# NANO103.net
KiCad netlist of a schematic drawn in Altium Designer
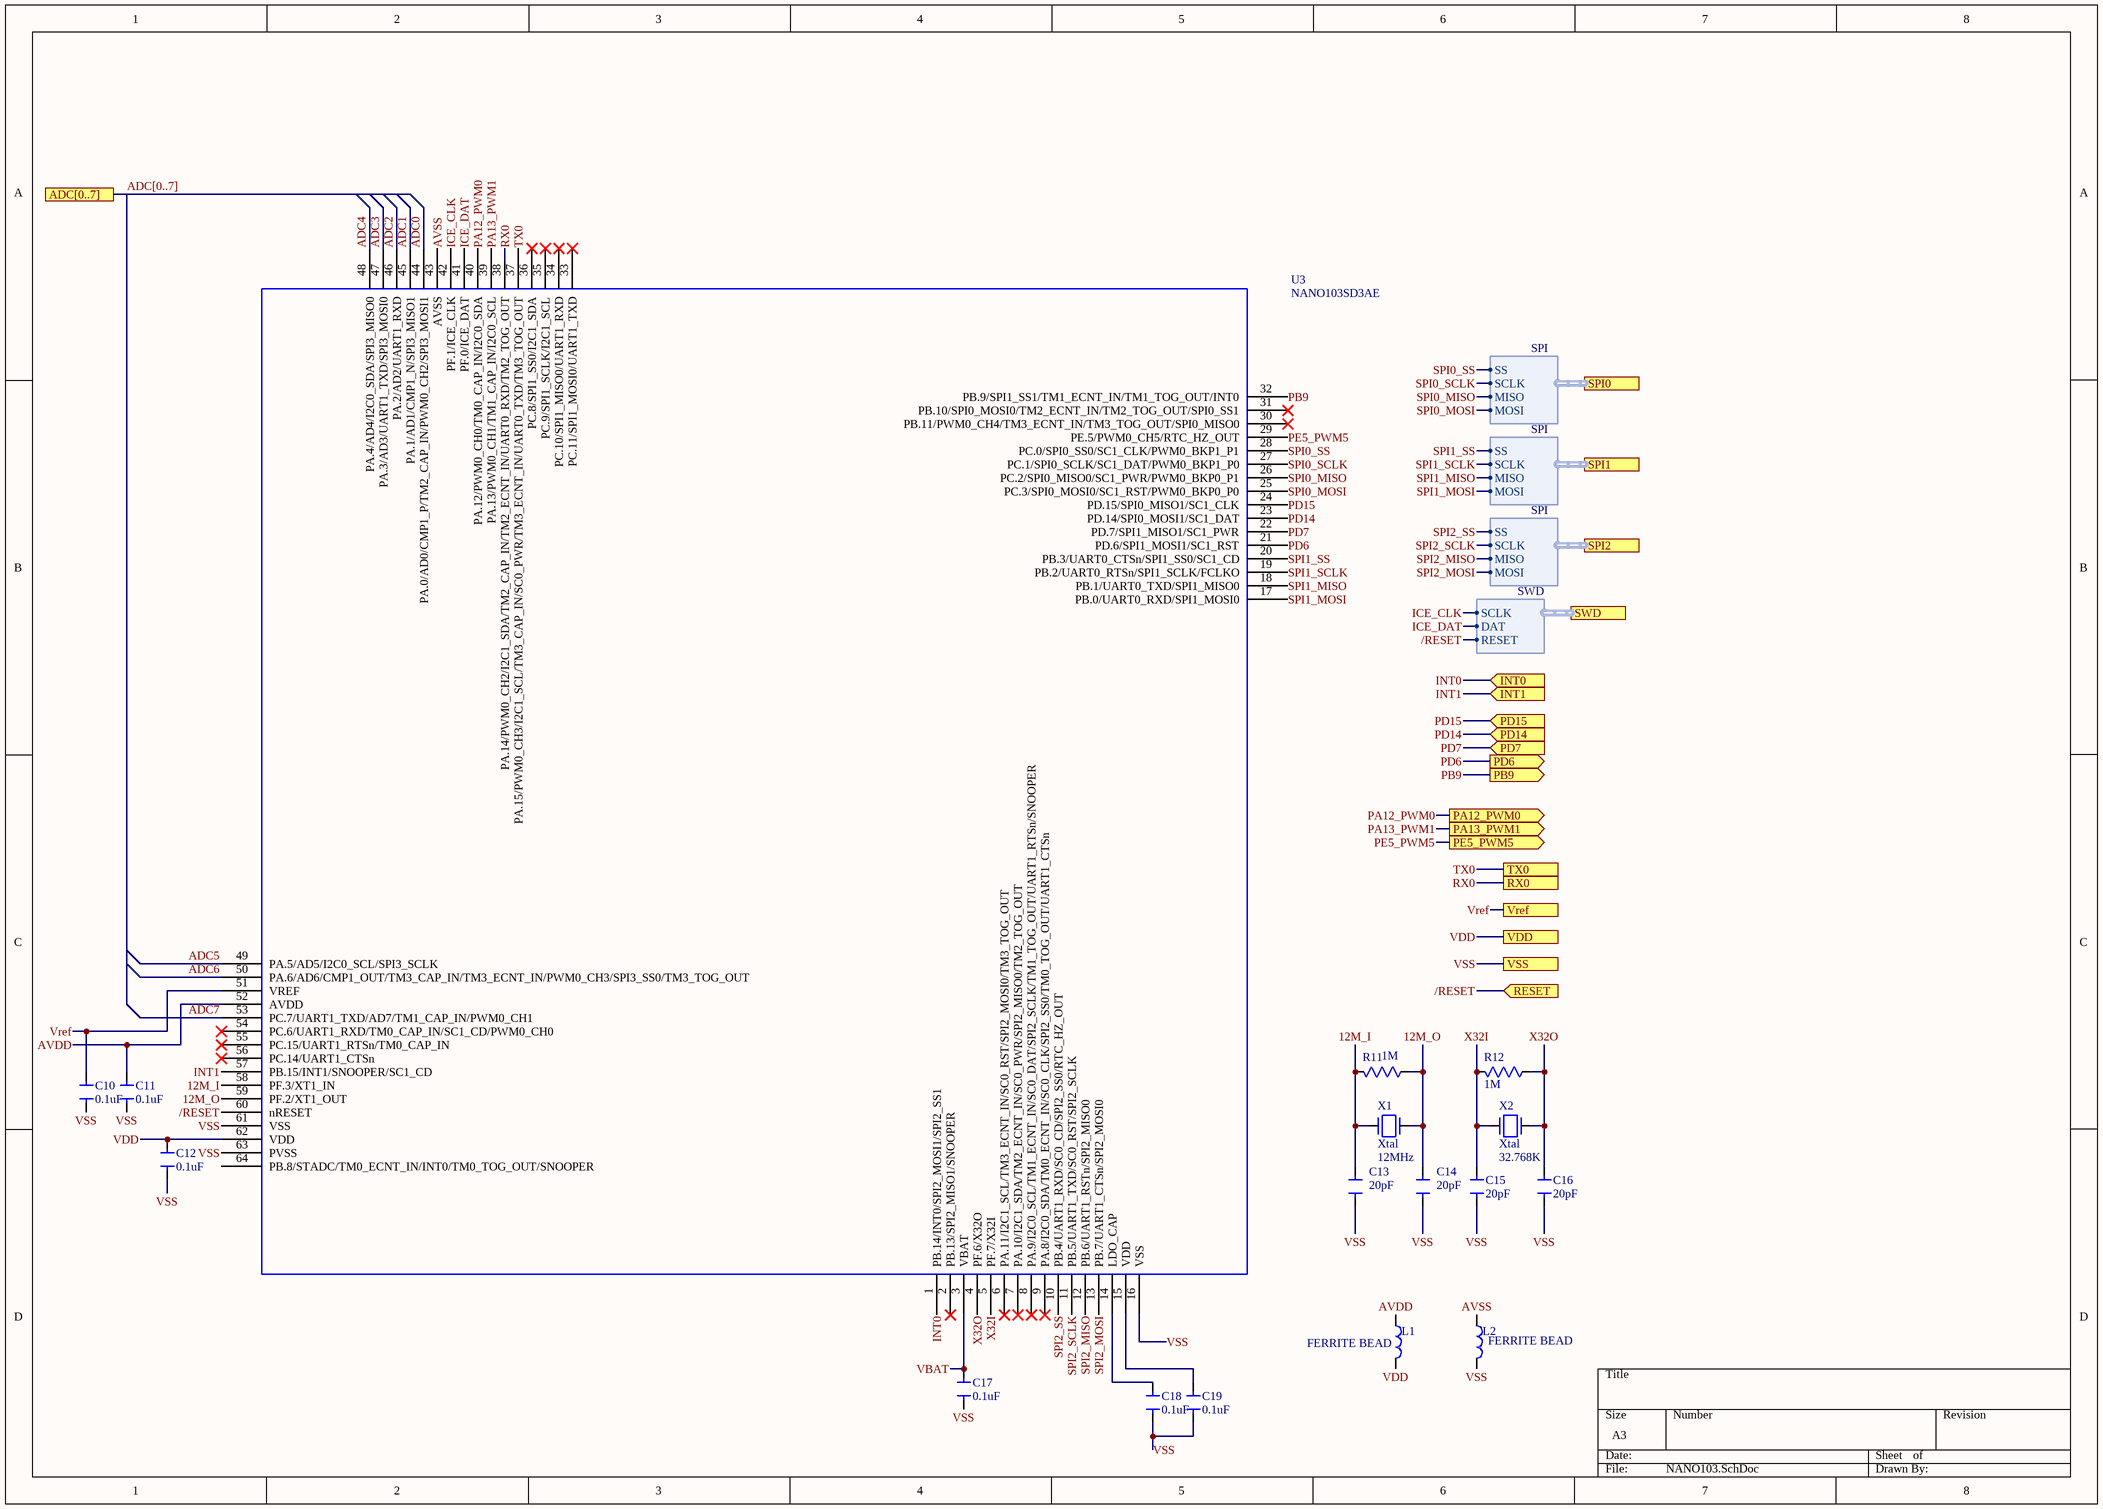
[diagram p0: NANO103.SchDoc]

(export (version "E")
  (design (tool "Eeschema 10.0.6"))
  (components
    (comp (ref "C10")
      (value "0.1uF")
      (footprint "CAP_0402")
      (fields (field (name "Comment") "Cap"))
      (libsource (lib "ZGR") (part "Cap"))
    )
    (comp (ref "C11")
      (value "0.1uF")
      (footprint "CAP_0402")
      (fields (field (name "Comment") "Cap"))
      (libsource (lib "ZGR") (part "Cap"))
    )
    (comp (ref "C12")
      (value "0.1uF")
      (footprint "CAP_0402")
      (fields (field (name "Comment") "Cap"))
      (libsource (lib "ZGR") (part "Cap"))
    )
    (comp (ref "C13")
      (value "20pF")
      (footprint "CAP_0402")
      (fields (field (name "Comment") "Cap"))
      (libsource (lib "ZGR") (part "Cap"))
    )
    (comp (ref "C14")
      (value "20pF")
      (footprint "CAP_0402")
      (fields (field (name "Comment") "Cap"))
      (libsource (lib "ZGR") (part "Cap"))
    )
    (comp (ref "C15")
      (value "20pF")
      (footprint "CAP_0402")
      (fields (field (name "Comment") "Cap"))
      (libsource (lib "ZGR") (part "Cap"))
    )
    (comp (ref "C16")
      (value "20pF")
      (footprint "CAP_0402")
      (fields (field (name "Comment") "Cap"))
      (libsource (lib "ZGR") (part "Cap"))
    )
    (comp (ref "C17")
      (value "0.1uF")
      (footprint "CAP_0402")
      (fields (field (name "Comment") "Cap"))
      (libsource (lib "ZGR") (part "Cap"))
    )
    (comp (ref "C18")
      (value "0.1uF")
      (footprint "CAP_0402")
      (fields (field (name "Comment") "Cap"))
      (libsource (lib "ZGR") (part "Cap"))
    )
    (comp (ref "C19")
      (value "0.1uF")
      (footprint "CAP_0402")
      (fields (field (name "Comment") "Cap"))
      (libsource (lib "ZGR") (part "Cap"))
    )
    (comp (ref "L1")
      (value "FERRITE BEAD")
      (footprint "Inductor_0603")
      (libsource (lib "ZGR") (part "Inductor"))
    )
    (comp (ref "L2")
      (value "FERRITE BEAD")
      (footprint "Inductor_0603")
      (libsource (lib "ZGR") (part "Inductor"))
    )
    (comp (ref "R11")
      (value "1M")
      (footprint "RES_0402")
      (fields (field (name "Comment") "Res"))
      (libsource (lib "ZGR") (part "Res"))
    )
    (comp (ref "R12")
      (value "1M")
      (footprint "RES_0402")
      (fields (field (name "Comment") "Res"))
      (libsource (lib "ZGR") (part "Res"))
    )
    (comp (ref "U3")
      (value "NANO103SD3AE")
      (footprint "MCU_LQFP_64_7x7")
      (libsource (lib "NUVOTON") (part "NANO103SD3AE"))
    )
    (comp (ref "X1")
      (value "Xtal")
      (footprint "2520S")
      (fields (field (name "ALTIUM_VALUE") "12MHz"))
      (libsource (lib "ZGR") (part "Xtal"))
    )
    (comp (ref "X2")
      (value "Xtal")
      (footprint "FC-135")
      (fields (field (name "ALTIUM_VALUE") "32.768K"))
      (libsource (lib "ZGR") (part "Xtal"))
    )
  )
  (nets
    (net (code "3") (name "/12M_I") (class "Default")
      (node (ref "C13") (pin "1") (pinfunction "1_1") (pintype "passive"))
      (node (ref "R11") (pin "1") (pinfunction "1_1") (pintype "passive"))
      (node (ref "U3") (pin "58") (pinfunction "PF.3/XT1_IN_58") (pintype "passive"))
      (node (ref "X1") (pin "2") (pintype "passive"))
    )
    (net (code "4") (name "/12M_O") (class "Default")
      (node (ref "C14") (pin "1") (pinfunction "1_1") (pintype "passive"))
      (node (ref "R11") (pin "2") (pinfunction "2_2") (pintype "passive"))
      (node (ref "U3") (pin "59") (pinfunction "PF.2/XT1_OUT_59") (pintype "passive"))
      (node (ref "X1") (pin "1") (pintype "passive"))
    )
    (net (code "5") (name "/ADC0") (class "Default")
      (node (ref "U3") (pin "44") (pinfunction "PA.0/AD0/CMP1_P/TM2_CAP_IN/PWM0_CH2/SPI3_MOSI1_44") (pintype "passive"))
    )
    (net (code "6") (name "/ADC1") (class "Default")
      (node (ref "U3") (pin "45") (pinfunction "PA.1/AD1/CMP1_N/SPI3_MISO1_45") (pintype "passive"))
    )
    (net (code "7") (name "/ADC2") (class "Default")
      (node (ref "U3") (pin "46") (pinfunction "PA.2/AD2/UART1_RXD_46") (pintype "passive"))
    )
    (net (code "8") (name "/ADC3") (class "Default")
      (node (ref "U3") (pin "47") (pinfunction "PA.3/AD3/UART1_TXD/SPI3_MOSI0_47") (pintype "passive"))
    )
    (net (code "9") (name "/ADC4") (class "Default")
      (node (ref "U3") (pin "48") (pinfunction "PA.4/AD4/I2C0_SDA/SPI3_MISO0_48") (pintype "passive"))
    )
    (net (code "10") (name "/ADC5") (class "Default")
      (node (ref "U3") (pin "49") (pinfunction "PA.5/AD5/I2C0_SCL/SPI3_SCLK_49") (pintype "passive"))
    )
    (net (code "11") (name "/ADC6") (class "Default")
      (node (ref "U3") (pin "50") (pinfunction "PA.6/AD6/CMP1_OUT/TM3_CAP_IN/TM3_ECNT_IN/PWM0_CH3/SPI3_SS0/TM3_TOG_OUT_50") (pintype "passive"))
    )
    (net (code "12") (name "/ADC7") (class "Default")
      (node (ref "U3") (pin "53") (pinfunction "PC.7/UART1_TXD/AD7/TM1_CAP_IN/PWM0_CH1_53") (pintype "passive"))
    )
    (net (code "14") (name "/AVDD") (class "Default")
      (node (ref "C11") (pin "2") (pinfunction "2_2") (pintype "passive"))
      (node (ref "L1") (pin "1") (pinfunction "1_1") (pintype "passive"))
      (node (ref "U3") (pin "52") (pinfunction "AVDD_52") (pintype "passive"))
    )
    (net (code "15") (name "/AVSS") (class "Default")
      (node (ref "L2") (pin "1") (pinfunction "1_1") (pintype "passive"))
      (node (ref "U3") (pin "43") (pinfunction "AVSS_43") (pintype "passive"))
    )
    (net (code "16") (name "/ICE_CLK") (class "Default")
      (node (ref "U3") (pin "42") (pinfunction "PF.1/ICE_CLK_42") (pintype "passive"))
    )
    (net (code "17") (name "/ICE_DAT") (class "Default")
      (node (ref "U3") (pin "41") (pinfunction "PF.0/ICE_DAT_41") (pintype "passive"))
    )
    (net (code "18") (name "/INT0") (class "Default")
      (node (ref "U3") (pin "1") (pinfunction "PB.14/INT0/SPI2_MOSI1/SPI2_SS1_1") (pintype "passive"))
    )
    (net (code "19") (name "/INT1") (class "Default")
      (node (ref "U3") (pin "57") (pinfunction "PB.15/INT1/SNOOPER/SC1_CD_57") (pintype "passive"))
    )
    (net (code "20") (name "/PA12_PWM0") (class "Default")
      (node (ref "U3") (pin "40") (pinfunction "PA.12/PWM0_CH0/TM0_CAP_IN/I2C0_SDA_40") (pintype "passive"))
    )
    (net (code "21") (name "/PA13_PWM1") (class "Default")
      (node (ref "U3") (pin "39") (pinfunction "PA.13/PWM0_CH1/TM1_CAP_IN/I2C0_SCL_39") (pintype "passive"))
    )
    (net (code "22") (name "/PB9") (class "Default")
      (node (ref "U3") (pin "32") (pinfunction "PB.9/SPI1_SS1/TM1_ECNT_IN/TM1_TOG_OUT/INT0_32") (pintype "passive"))
    )
    (net (code "23") (name "/PD6") (class "Default")
      (node (ref "U3") (pin "21") (pinfunction "PD.6/SPI1_MOSI1/SC1_RST_21") (pintype "passive"))
    )
    (net (code "24") (name "/PD7") (class "Default")
      (node (ref "U3") (pin "22") (pinfunction "PD.7/SPI1_MISO1/SC1_PWR_22") (pintype "passive"))
    )
    (net (code "25") (name "/PD14") (class "Default")
      (node (ref "U3") (pin "23") (pinfunction "PD.14/SPI0_MOSI1/SC1_DAT_23") (pintype "passive"))
    )
    (net (code "26") (name "/PD15") (class "Default")
      (node (ref "U3") (pin "24") (pinfunction "PD.15/SPI0_MISO1/SC1_CLK_24") (pintype "passive"))
    )
    (net (code "27") (name "/PE5_PWM5") (class "Default")
      (node (ref "U3") (pin "29") (pinfunction "PE.5/PWM0_CH5/RTC_HZ_OUT_29") (pintype "passive"))
    )
    (net (code "28") (name "/RX0") (class "Default")
      (node (ref "U3") (pin "38") (pinfunction "PA.14/PWM0_CH2/I2C1_SDA/TM2_CAP_IN/TM2_ECNT_IN/UART0_RXD/TM2_TOG_OUT_38") (pintype "passive"))
    )
    (net (code "29") (name "/SPI0_MISO") (class "Default")
      (node (ref "U3") (pin "26") (pinfunction "PC.2/SPI0_MISO0/SC1_PWR/PWM0_BKP0_P1_26") (pintype "passive"))
    )
    (net (code "30") (name "/SPI0_MOSI") (class "Default")
      (node (ref "U3") (pin "25") (pinfunction "PC.3/SPI0_MOSI0/SC1_RST/PWM0_BKP0_P0_25") (pintype "passive"))
    )
    (net (code "31") (name "/SPI0_SCLK") (class "Default")
      (node (ref "U3") (pin "27") (pinfunction "PC.1/SPI0_SCLK/SC1_DAT/PWM0_BKP1_P0_27") (pintype "passive"))
    )
    (net (code "32") (name "/SPI0_SS") (class "Default")
      (node (ref "U3") (pin "28") (pinfunction "PC.0/SPI0_SS0/SC1_CLK/PWM0_BKP1_P1_28") (pintype "passive"))
    )
    (net (code "33") (name "/SPI1_MISO") (class "Default")
      (node (ref "U3") (pin "18") (pinfunction "PB.1/UART0_TXD/SPI1_MISO0_18") (pintype "passive"))
    )
    (net (code "34") (name "/SPI1_MOSI") (class "Default")
      (node (ref "U3") (pin "17") (pinfunction "PB.0/UART0_RXD/SPI1_MOSI0_17") (pintype "passive"))
    )
    (net (code "35") (name "/SPI1_SCLK") (class "Default")
      (node (ref "U3") (pin "19") (pinfunction "PB.2/UART0_RTSn/SPI1_SCLK/FCLKO_19") (pintype "passive"))
    )
    (net (code "36") (name "/SPI1_SS") (class "Default")
      (node (ref "U3") (pin "20") (pinfunction "PB.3/UART0_CTSn/SPI1_SS0/SC1_CD_20") (pintype "passive"))
    )
    (net (code "37") (name "/SPI2_MISO") (class "Default")
      (node (ref "U3") (pin "12") (pinfunction "PB.6/UART1_RSTn/SPI2_MISO0_12") (pintype "passive"))
    )
    (net (code "38") (name "/SPI2_MOSI") (class "Default")
      (node (ref "U3") (pin "13") (pinfunction "PB.7/UART1_CTSn/SPI2_MOSI0_13") (pintype "passive"))
    )
    (net (code "39") (name "/SPI2_SCLK") (class "Default")
      (node (ref "U3") (pin "11") (pinfunction "PB.5/UART1_TXD/SC0_RST/SPI2_SCLK_11") (pintype "passive"))
    )
    (net (code "40") (name "/SPI2_SS") (class "Default")
      (node (ref "U3") (pin "10") (pinfunction "PB.4/UART1_RXD/SC0_CD/SPI2_SS0/RTC_HZ_OUT_10") (pintype "passive"))
    )
    (net (code "41") (name "/TX0") (class "Default")
      (node (ref "U3") (pin "37") (pinfunction "PA.15/PWM0_CH3/I2C1_SCL/TM3_CAP_IN/SC0_PWR/TM3_ECNT_IN/UART0_TXD/TM3_TOG_OUT_37") (pintype "passive"))
    )
    (net (code "42") (name "/VBAT") (class "Default")
      (node (ref "C17") (pin "2") (pinfunction "2_2") (pintype "passive"))
      (node (ref "U3") (pin "3") (pinfunction "VBAT_3") (pintype "passive"))
    )
    (net (code "43") (name "/VDD") (class "Default")
      (node (ref "C12") (pin "2") (pinfunction "2_2") (pintype "passive"))
      (node (ref "L1") (pin "2") (pinfunction "2_2") (pintype "passive"))
      (node (ref "U3") (pin "62") (pinfunction "VDD_62") (pintype "passive"))
    )
    (net (code "44") (name "/VSS") (class "Default")
      (node (ref "C10") (pin "1") (pinfunction "1_1") (pintype "passive"))
      (node (ref "C11") (pin "1") (pinfunction "1_1") (pintype "passive"))
      (node (ref "C12") (pin "1") (pinfunction "1_1") (pintype "passive"))
      (node (ref "C13") (pin "2") (pinfunction "2_2") (pintype "passive"))
      (node (ref "C14") (pin "2") (pinfunction "2_2") (pintype "passive"))
      (node (ref "C15") (pin "2") (pinfunction "2_2") (pintype "passive"))
      (node (ref "C16") (pin "2") (pinfunction "2_2") (pintype "passive"))
      (node (ref "C17") (pin "1") (pinfunction "1_1") (pintype "passive"))
      (node (ref "C18") (pin "1") (pinfunction "1_1") (pintype "passive"))
      (node (ref "C19") (pin "1") (pinfunction "1_1") (pintype "passive"))
      (node (ref "L2") (pin "2") (pinfunction "2_2") (pintype "passive"))
      (node (ref "U3") (pin "16") (pinfunction "VSS_16") (pintype "passive"))
      (node (ref "U3") (pin "61") (pinfunction "VSS_61") (pintype "passive"))
      (node (ref "U3") (pin "63") (pinfunction "PVSS_63") (pintype "passive"))
    )
    (net (code "45") (name "/Vref") (class "Default")
      (node (ref "C10") (pin "2") (pinfunction "2_2") (pintype "passive"))
      (node (ref "U3") (pin "51") (pinfunction "VREF_51") (pintype "passive"))
    )
    (net (code "46") (name "/X32I") (class "Default")
      (node (ref "C15") (pin "1") (pinfunction "1_1") (pintype "passive"))
      (node (ref "R12") (pin "1") (pinfunction "1_1") (pintype "passive"))
      (node (ref "U3") (pin "5") (pinfunction "PF.7/X32I_5") (pintype "passive"))
      (node (ref "X2") (pin "2") (pintype "passive"))
    )
    (net (code "47") (name "/X32O") (class "Default")
      (node (ref "C16") (pin "1") (pinfunction "1_1") (pintype "passive"))
      (node (ref "R12") (pin "2") (pinfunction "2_2") (pintype "passive"))
      (node (ref "U3") (pin "4") (pinfunction "PF.6/X32O_4") (pintype "passive"))
      (node (ref "X2") (pin "1") (pintype "passive"))
    )
    (net (code "50") (name "/{slash}RESET") (class "Default")
      (node (ref "U3") (pin "60") (pinfunction "nRESET_60") (pintype "passive"))
    )
    (net (code "51") (name "Net-(C19-Pad2)") (class "Default")
      (node (ref "C19") (pin "2") (pinfunction "2_2") (pintype "passive"))
      (node (ref "U3") (pin "15") (pinfunction "VDD_15") (pintype "passive"))
    )
    (net (code "52") (name "Net-(U3-LDO_CAP)") (class "Default")
      (node (ref "C18") (pin "2") (pinfunction "2_2") (pintype "passive"))
      (node (ref "U3") (pin "14") (pinfunction "LDO_CAP_14") (pintype "passive"))
    )
    (net (code "53") (name "unconnected-(U3-PA.8{slash}I2C0_SDA{slash}TM0_ECNT_IN{slash}SC0_CLK{slash}SPI2_SS0{slash}TM0_TOG_OUT{slash}UART1_CTSn-Pad9)") (class "Default")
      (node (ref "U3") (pin "9") (pinfunction "PA.8/I2C0_SDA/TM0_ECNT_IN/SC0_CLK/SPI2_SS0/TM0_TOG_OUT/UART1_CTSn_9") (pintype "passive+no_connect"))
    )
    (net (code "54") (name "unconnected-(U3-PA.9{slash}I2C0_SCL{slash}TM1_ECNT_IN{slash}SC0_DAT{slash}SPI2_SCLK{slash}TM1_TOG_OUT{slash}UART1_RTSn{slash}SNOOPER-Pad8)") (class "Default")
      (node (ref "U3") (pin "8") (pinfunction "PA.9/I2C0_SCL/TM1_ECNT_IN/SC0_DAT/SPI2_SCLK/TM1_TOG_OUT/UART1_RTSn/SNOOPER_8") (pintype "passive+no_connect"))
    )
    (net (code "55") (name "unconnected-(U3-PA.10{slash}I2C1_SDA{slash}TM2_ECNT_IN{slash}SC0_PWR{slash}SPI2_MISO0{slash}TM2_TOG_OUT-Pad7)") (class "Default")
      (node (ref "U3") (pin "7") (pinfunction "PA.10/I2C1_SDA/TM2_ECNT_IN/SC0_PWR/SPI2_MISO0/TM2_TOG_OUT_7") (pintype "passive+no_connect"))
    )
    (net (code "56") (name "unconnected-(U3-PA.11{slash}I2C1_SCL{slash}TM3_ECNT_IN{slash}SC0_RST{slash}SPI2_MOSI0{slash}TM3_TOG_OUT-Pad6)") (class "Default")
      (node (ref "U3") (pin "6") (pinfunction "PA.11/I2C1_SCL/TM3_ECNT_IN/SC0_RST/SPI2_MOSI0/TM3_TOG_OUT_6") (pintype "passive+no_connect"))
    )
    (net (code "57") (name "unconnected-(U3-PB.8{slash}STADC{slash}TM0_ECNT_IN{slash}INT0{slash}TM0_TOG_OUT{slash}SNOOPER-Pad64)") (class "Default")
      (node (ref "U3") (pin "64") (pinfunction "PB.8/STADC/TM0_ECNT_IN/INT0/TM0_TOG_OUT/SNOOPER_64") (pintype "passive"))
    )
    (net (code "58") (name "unconnected-(U3-PB.10{slash}SPI0_MOSI0{slash}TM2_ECNT_IN{slash}TM2_TOG_OUT{slash}SPI0_SS1-Pad31)") (class "Default")
      (node (ref "U3") (pin "31") (pinfunction "PB.10/SPI0_MOSI0/TM2_ECNT_IN/TM2_TOG_OUT/SPI0_SS1_31") (pintype "passive+no_connect"))
    )
    (net (code "59") (name "unconnected-(U3-PB.11{slash}PWM0_CH4{slash}TM3_ECNT_IN{slash}TM3_TOG_OUT{slash}SPI0_MISO0-Pad30)") (class "Default")
      (node (ref "U3") (pin "30") (pinfunction "PB.11/PWM0_CH4/TM3_ECNT_IN/TM3_TOG_OUT/SPI0_MISO0_30") (pintype "passive+no_connect"))
    )
    (net (code "60") (name "unconnected-(U3-PB.13{slash}SPI2_MISO1{slash}SNOOPER-Pad2)") (class "Default")
      (node (ref "U3") (pin "2") (pinfunction "PB.13/SPI2_MISO1/SNOOPER_2") (pintype "passive+no_connect"))
    )
    (net (code "61") (name "unconnected-(U3-PC.6{slash}UART1_RXD{slash}TM0_CAP_IN{slash}SC1_CD{slash}PWM0_CH0-Pad54)") (class "Default")
      (node (ref "U3") (pin "54") (pinfunction "PC.6/UART1_RXD/TM0_CAP_IN/SC1_CD/PWM0_CH0_54") (pintype "passive+no_connect"))
    )
    (net (code "62") (name "unconnected-(U3-PC.8{slash}SPI1_SS0{slash}I2C1_SDA-Pad36)") (class "Default")
      (node (ref "U3") (pin "36") (pinfunction "PC.8/SPI1_SS0/I2C1_SDA_36") (pintype "passive+no_connect"))
    )
    (net (code "63") (name "unconnected-(U3-PC.9{slash}SPI1_SCLK{slash}I2C1_SCL-Pad35)") (class "Default")
      (node (ref "U3") (pin "35") (pinfunction "PC.9/SPI1_SCLK/I2C1_SCL_35") (pintype "passive+no_connect"))
    )
    (net (code "64") (name "unconnected-(U3-PC.10{slash}SPI1_MISO0{slash}UART1_RXD-Pad34)") (class "Default")
      (node (ref "U3") (pin "34") (pinfunction "PC.10/SPI1_MISO0/UART1_RXD_34") (pintype "passive+no_connect"))
    )
    (net (code "65") (name "unconnected-(U3-PC.11{slash}SPI1_MOSI0{slash}UART1_TXD-Pad33)") (class "Default")
      (node (ref "U3") (pin "33") (pinfunction "PC.11/SPI1_MOSI0/UART1_TXD_33") (pintype "passive+no_connect"))
    )
    (net (code "66") (name "unconnected-(U3-PC.14{slash}UART1_CTSn-Pad56)") (class "Default")
      (node (ref "U3") (pin "56") (pinfunction "PC.14/UART1_CTSn_56") (pintype "passive+no_connect"))
    )
    (net (code "67") (name "unconnected-(U3-PC.15{slash}UART1_RTSn{slash}TM0_CAP_IN-Pad55)") (class "Default")
      (node (ref "U3") (pin "55") (pinfunction "PC.15/UART1_RTSn/TM0_CAP_IN_55") (pintype "passive+no_connect"))
    )
  )
)
